# 1U_Mini_BusBoard.net
KiCad netlist of a schematic drawn in EAGLE
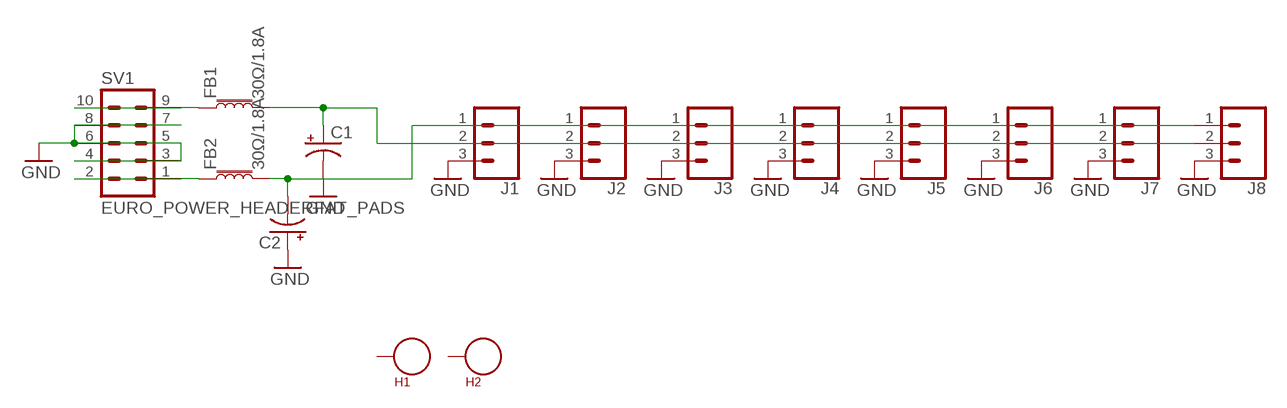
[diagram p0: schematic, sheet 1]

(export (version "E")
  (design (tool "Eeschema 10.0.6"))
  (components
    (comp (ref "C1")
      (value "CPOL-USC")
      (footprint "eagle-import:PANASONIC_C")
      (libsource (lib "eagle-import") (part "CPOL-USC"))
    )
    (comp (ref "C2")
      (value "CPOL-USC")
      (footprint "eagle-import:PANASONIC_C")
      (libsource (lib "eagle-import") (part "CPOL-USC"))
    )
    (comp (ref "FB1")
      (value "30Ω/1.8A")
      (footprint "eagle-import:0603")
      (libsource (lib "eagle-import") (part "FERRITE_BEAD-0603"))
    )
    (comp (ref "FB2")
      (value "30Ω/1.8A")
      (footprint "eagle-import:0603")
      (libsource (lib "eagle-import") (part "FERRITE_BEAD-0603"))
    )
    (comp (ref "H1")
      (value "SEW_HOLE")
      (footprint "eagle-import:SIMPLE_HOLE")
      (libsource (lib "eagle-import") (part "SEW_HOLE"))
    )
    (comp (ref "H2")
      (value "SEW_HOLE")
      (footprint "eagle-import:SIMPLE_HOLE")
      (libsource (lib "eagle-import") (part "SEW_HOLE"))
    )
    (comp (ref "J1")
      (value "CONN_031X03_NO_SILK")
      (footprint "eagle-import:1X03_NO_SILK")
      (libsource (lib "eagle-import") (part "CONN_031X03_NO_SILK"))
    )
    (comp (ref "J2")
      (value "CONN_031X03_NO_SILK")
      (footprint "eagle-import:1X03_NO_SILK")
      (libsource (lib "eagle-import") (part "CONN_031X03_NO_SILK"))
    )
    (comp (ref "J3")
      (value "CONN_031X03_NO_SILK")
      (footprint "eagle-import:1X03_NO_SILK")
      (libsource (lib "eagle-import") (part "CONN_031X03_NO_SILK"))
    )
    (comp (ref "J4")
      (value "CONN_031X03_NO_SILK")
      (footprint "eagle-import:1X03_NO_SILK")
      (libsource (lib "eagle-import") (part "CONN_031X03_NO_SILK"))
    )
    (comp (ref "J5")
      (value "CONN_031X03_NO_SILK")
      (footprint "eagle-import:1X03_NO_SILK")
      (libsource (lib "eagle-import") (part "CONN_031X03_NO_SILK"))
    )
    (comp (ref "J6")
      (value "CONN_031X03_NO_SILK")
      (footprint "eagle-import:1X03_NO_SILK")
      (libsource (lib "eagle-import") (part "CONN_031X03_NO_SILK"))
    )
    (comp (ref "J7")
      (value "CONN_031X03_NO_SILK")
      (footprint "eagle-import:1X03_NO_SILK")
      (libsource (lib "eagle-import") (part "CONN_031X03_NO_SILK"))
    )
    (comp (ref "J8")
      (value "CONN_031X03_NO_SILK")
      (footprint "eagle-import:1X03_NO_SILK")
      (libsource (lib "eagle-import") (part "CONN_031X03_NO_SILK"))
    )
    (comp (ref "SV1")
      (value "EURO_POWER_HEADERFAT_PADS")
      (footprint "eagle-import:EURO_PWR_HEADER_FAT")
      (libsource (lib "eagle-import") (part "EURO_POWER_HEADERFAT_PADS"))
    )
  )
  (nets
    (net (code "1") (name "GND") (class "Default")
      (node (ref "C1") (pin "-") (pinfunction "-_-") (pintype "passive"))
      (node (ref "C2") (pin "+") (pinfunction "+_+") (pintype "passive"))
      (node (ref "J1") (pin "3") (pinfunction "3_3") (pintype "passive"))
      (node (ref "J2") (pin "3") (pinfunction "3_3") (pintype "passive"))
      (node (ref "J3") (pin "3") (pinfunction "3_3") (pintype "passive"))
      (node (ref "J4") (pin "3") (pinfunction "3_3") (pintype "passive"))
      (node (ref "J5") (pin "3") (pinfunction "3_3") (pintype "passive"))
      (node (ref "J6") (pin "3") (pinfunction "3_3") (pintype "passive"))
      (node (ref "J7") (pin "3") (pinfunction "3_3") (pintype "passive"))
      (node (ref "J8") (pin "3") (pinfunction "3_3") (pintype "passive"))
      (node (ref "SV1") (pin "3") (pinfunction "3_3") (pintype "passive"))
      (node (ref "SV1") (pin "4") (pinfunction "4_4") (pintype "passive"))
      (node (ref "SV1") (pin "5") (pinfunction "5_5") (pintype "passive"))
      (node (ref "SV1") (pin "6") (pinfunction "6_6") (pintype "passive"))
      (node (ref "SV1") (pin "7") (pinfunction "7_7") (pintype "passive"))
      (node (ref "SV1") (pin "8") (pinfunction "8_8") (pintype "passive"))
    )
    (net (code "2") (name "Net-(C1-Pad+)") (class "Default")
      (node (ref "C1") (pin "+") (pinfunction "+_+") (pintype "passive"))
      (node (ref "FB1") (pin "2") (pinfunction "2_2") (pintype "passive"))
      (node (ref "J1") (pin "2") (pinfunction "2_2") (pintype "passive"))
      (node (ref "J2") (pin "2") (pinfunction "2_2") (pintype "passive"))
      (node (ref "J3") (pin "2") (pinfunction "2_2") (pintype "passive"))
      (node (ref "J4") (pin "2") (pinfunction "2_2") (pintype "passive"))
      (node (ref "J5") (pin "2") (pinfunction "2_2") (pintype "passive"))
      (node (ref "J6") (pin "2") (pinfunction "2_2") (pintype "passive"))
      (node (ref "J7") (pin "2") (pinfunction "2_2") (pintype "passive"))
      (node (ref "J8") (pin "2") (pinfunction "2_2") (pintype "passive"))
    )
    (net (code "3") (name "Net-(C2-Pad-)") (class "Default")
      (node (ref "C2") (pin "-") (pinfunction "-_-") (pintype "passive"))
      (node (ref "FB2") (pin "2") (pinfunction "2_2") (pintype "passive"))
      (node (ref "J1") (pin "1") (pinfunction "1_1") (pintype "passive"))
      (node (ref "J2") (pin "1") (pinfunction "1_1") (pintype "passive"))
      (node (ref "J3") (pin "1") (pinfunction "1_1") (pintype "passive"))
      (node (ref "J4") (pin "1") (pinfunction "1_1") (pintype "passive"))
      (node (ref "J5") (pin "1") (pinfunction "1_1") (pintype "passive"))
      (node (ref "J6") (pin "1") (pinfunction "1_1") (pintype "passive"))
      (node (ref "J7") (pin "1") (pinfunction "1_1") (pintype "passive"))
      (node (ref "J8") (pin "1") (pinfunction "1_1") (pintype "passive"))
    )
    (net (code "4") (name "Net-(FB1-Pad1)") (class "Default")
      (node (ref "FB1") (pin "1") (pinfunction "1_1") (pintype "passive"))
      (node (ref "SV1") (pin "10") (pinfunction "10_10") (pintype "passive"))
      (node (ref "SV1") (pin "9") (pinfunction "9_9") (pintype "passive"))
    )
    (net (code "5") (name "Net-(FB2-Pad1)") (class "Default")
      (node (ref "FB2") (pin "1") (pinfunction "1_1") (pintype "passive"))
      (node (ref "SV1") (pin "1") (pinfunction "1_1") (pintype "passive"))
      (node (ref "SV1") (pin "2") (pinfunction "2_2") (pintype "passive"))
    )
    (net (code "6") (name "unconnected-(H1-PadP$1)") (class "Default")
      (node (ref "H1") (pin "P$1") (pinfunction "P$1_P$1") (pintype "bidirectional"))
    )
    (net (code "7") (name "unconnected-(H2-PadP$1)") (class "Default")
      (node (ref "H2") (pin "P$1") (pinfunction "P$1_P$1") (pintype "bidirectional"))
    )
  )
)
